# MCU.net
KiCad netlist of a schematic drawn in Altium Designer
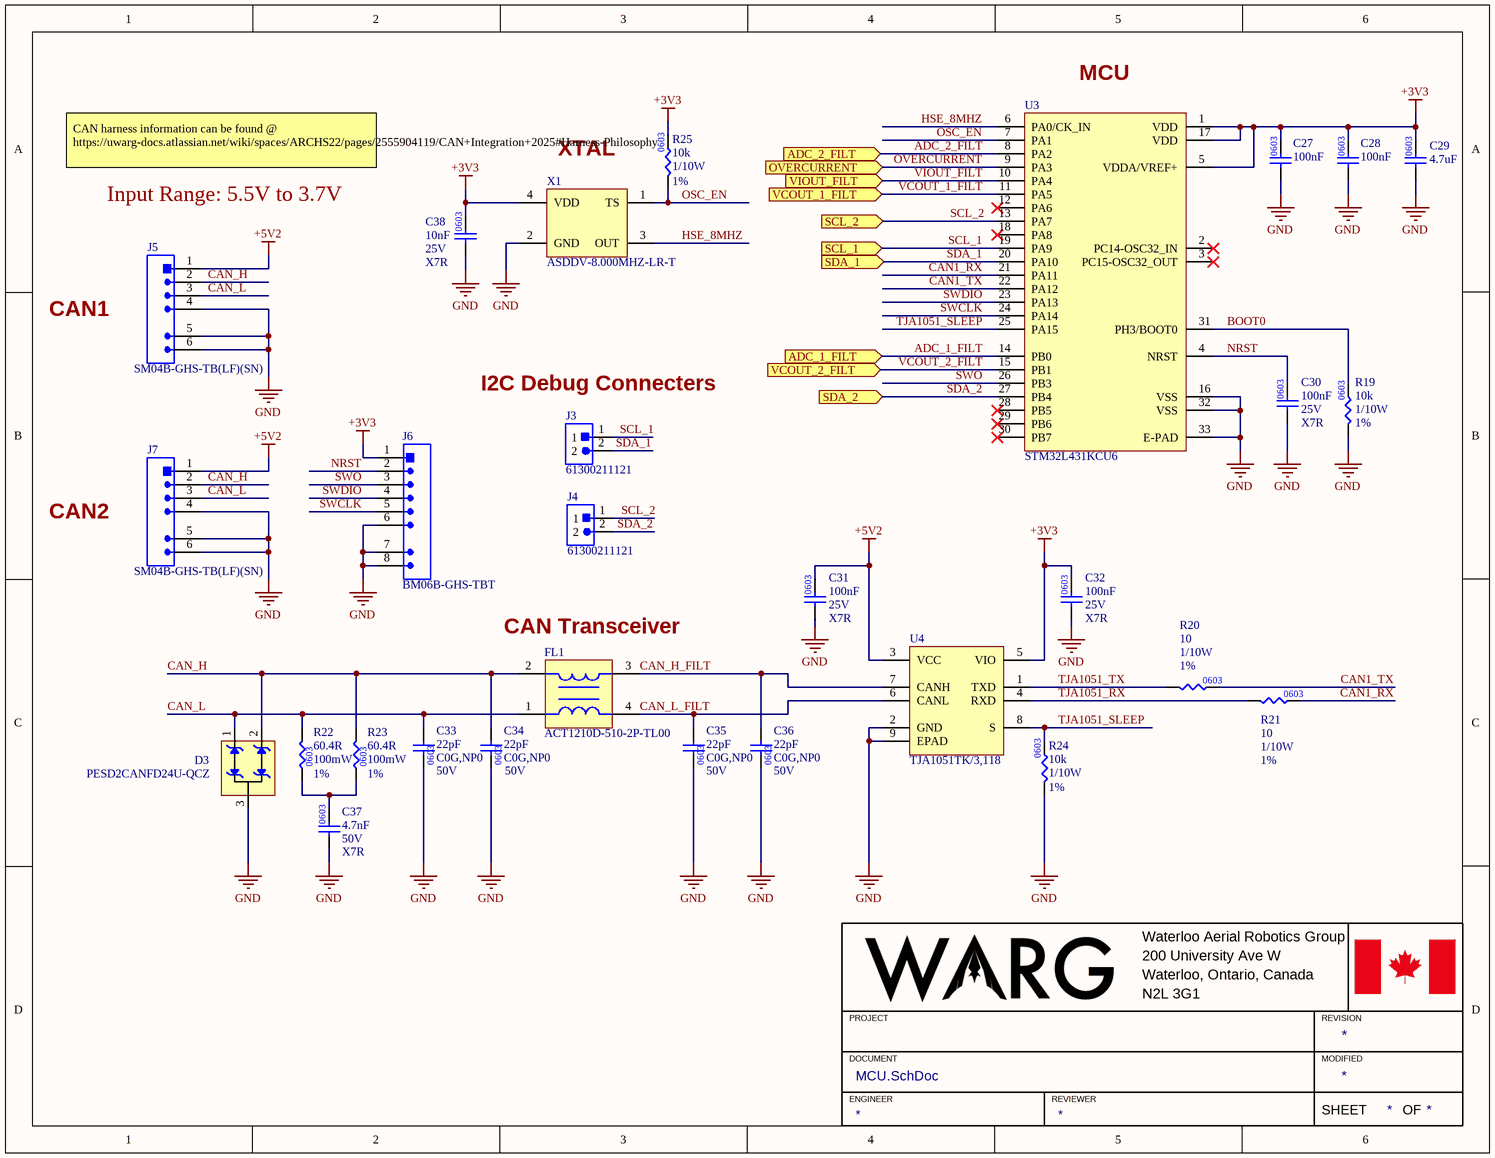
[diagram p0: MCU.SchDoc]

(export (version "E")
  (design (tool "Eeschema 10.0.6"))
  (components
    (comp (ref "C27")
      (value "100nF")
      (footprint ".CAP_0603-Footprint-1")
      (description "CAP CER 100nF 16V X7R 0603")
      (fields (field (name "VOLTAGE") "16V") (field (name "Comment") "GCM188R71C104KA37D"))
      (libsource (lib "WARG") (part ".CAP_0603-Symbol-1"))
    )
    (comp (ref "C28")
      (value "100nF")
      (footprint ".CAP_0603-Footprint-1")
      (description "CAP CER 100nF 16V X7R 0603")
      (fields (field (name "VOLTAGE") "16V") (field (name "Comment") "GCM188R71C104KA37D"))
      (libsource (lib "WARG") (part ".CAP_0603-Symbol-1"))
    )
    (comp (ref "C29")
      (value "4.7uF")
      (footprint ".CAP_0603-Footprint-1")
      (description "CAP CER 4.7uF 25V X6S 0603")
      (fields (field (name "VOLTAGE") "25V") (field (name "Comment") "GRM188C81E475KE11D"))
      (libsource (lib "WARG") (part ".CAP_0603-Symbol-1"))
    )
    (comp (ref "C30")
      (value "CL10B104KA8NNNC")
      (footprint ".CAP_0603-Footprint-1")
      (description "CAP CER 0.1UF 25V X7R 0603")
      (fields
        (field (name "TOLERANCE") "10%")
        (field (name "VOLTAGE RATING") "25V")
        (field (name "DIELECTRIC") "X7R")
        (field (name "CAPACITANCE") "100nF")
      )
      (libsource (lib "WARG") (part ".CAP_0603-Symbol-1"))
    )
    (comp (ref "C31")
      (value "CL10B104KA8NNNC")
      (footprint ".CAP_0603-Footprint-1")
      (description "CAP CER 0.1UF 25V X7R 0603")
      (fields
        (field (name "TOLERANCE") "10%")
        (field (name "VOLTAGE RATING") "25V")
        (field (name "DIELECTRIC") "X7R")
        (field (name "CAPACITANCE") "100nF")
      )
      (libsource (lib "WARG") (part ".CAP_0603-Symbol-1"))
    )
    (comp (ref "C32")
      (value "CL10B104KA8NNNC")
      (footprint ".CAP_0603-Footprint-1")
      (description "CAP CER 0.1UF 25V X7R 0603")
      (fields
        (field (name "TOLERANCE") "10%")
        (field (name "VOLTAGE RATING") "25V")
        (field (name "DIELECTRIC") "X7R")
        (field (name "CAPACITANCE") "100nF")
      )
      (libsource (lib "WARG") (part ".CAP_0603-Symbol-1"))
    )
    (comp (ref "C33")
      (value "22pF")
      (footprint ".CAP_0603-Footprint-1")
      (description "CAP CER 22PF 50V C0G/NPO 0603")
      (fields
        (field (name "TEMPERATURE COEFFICIENT") "C0G,NP0")
        (field (name "TOLERANCE") "5%")
        (field (name "VOLTAGE RATING") "50V")
        (field (name "Comment") "CC0603JRNPO9BN220")
      )
      (libsource (lib "WARG") (part ".CAP_0603-Symbol-1"))
    )
    (comp (ref "C34")
      (value "22pF")
      (footprint ".CAP_0603-Footprint-1")
      (description "CAP CER 22PF 50V C0G/NPO 0603")
      (fields
        (field (name "TEMPERATURE COEFFICIENT") "C0G,NP0")
        (field (name "TOLERANCE") "5%")
        (field (name "VOLTAGE RATING") "50V")
        (field (name "Comment") "CC0603JRNPO9BN220")
      )
      (libsource (lib "WARG") (part ".CAP_0603-Symbol-1"))
    )
    (comp (ref "C35")
      (value "22pF")
      (footprint ".CAP_0603-Footprint-1")
      (description "CAP CER 22PF 50V C0G/NPO 0603")
      (fields
        (field (name "TEMPERATURE COEFFICIENT") "C0G,NP0")
        (field (name "TOLERANCE") "5%")
        (field (name "VOLTAGE RATING") "50V")
        (field (name "Comment") "CC0603JRNPO9BN220")
      )
      (libsource (lib "WARG") (part ".CAP_0603-Symbol-1"))
    )
    (comp (ref "C36")
      (value "22pF")
      (footprint ".CAP_0603-Footprint-1")
      (description "CAP CER 22PF 50V C0G/NPO 0603")
      (fields
        (field (name "TEMPERATURE COEFFICIENT") "C0G,NP0")
        (field (name "TOLERANCE") "5%")
        (field (name "VOLTAGE RATING") "50V")
        (field (name "Comment") "CC0603JRNPO9BN220")
      )
      (libsource (lib "WARG") (part ".CAP_0603-Symbol-1"))
    )
    (comp (ref "C37")
      (value "4.7nF")
      (footprint ".CAP_0603-Footprint-1")
      (description "CAP CER 4700PF 50V X7R 0603")
      (fields
        (field (name "RATED DC VOLTAGE (URDC)") "50V")
        (field (name "TEMPERATURE CHARACTERISTICS CODE") "X7R")
        (field (name "Comment") "GCM188R71H472KA37D")
      )
      (libsource (lib "WARG") (part ".CAP_0603-Symbol-1"))
    )
    (comp (ref "C38")
      (value "CC0603KRX7R8BB103")
      (footprint ".CAP_0603-Footprint-1")
      (description "CAP CER 10nF 25V X7R 0603")
      (fields
        (field (name "TEMPERATURE COEFFICIENT") "X7R")
        (field (name "VOLTAGE RATING") "25V")
        (field (name "CAPACITANCE") "10nF")
      )
      (libsource (lib "WARG") (part ".CAP_0603-Symbol-1"))
    )
    (comp (ref "D3")
      (value "PESD2CANFD24U-QCZ")
      (footprint "PESD2CANFD24U-QCZ-Footprint-1")
      (description "TVS DIODE 24VWM 43VC DFN1412D-3")
      (libsource (lib "WARG") (part "PESD2CANFD24U-QCZ-Symbol-1"))
    )
    (comp (ref "FL1")
      (value "ACT1210D-510-2P-TL00")
      (footprint "ACT1210D-510-2P-TL00-Footprint-1")
      (description "CMC 50UH 115MA 2LN 2.3KOHM SMD")
      (libsource (lib "WARG") (part "ACT1210D-510-2P-TL00-Symbol-1"))
    )
    (comp (ref "J3")
      (value "61300211121")
      (footprint "61300211121")
      (description "CONN HEADER VERT 2POS 2.54MM")
      (libsource (lib "WARG") (part "61300211121"))
    )
    (comp (ref "J4")
      (value "61300211121")
      (footprint "61300211121")
      (description "CONN HEADER VERT 2POS 2.54MM")
      (libsource (lib "WARG") (part "61300211121"))
    )
    (comp (ref "J5")
      (value "SM04B-GHS-TB(LF)(SN)")
      (footprint "CONN_SM04B-GHS-TB_JST")
      (description "Conn Shrouded Header HDR 4 POS 1.25mm Solder RA SMD Reel")
      (libsource (lib "WARG") (part "SM04B-GHS-TB(LF)(SN)"))
    )
    (comp (ref "J6")
      (value "BM06B-GHS-TBT")
      (footprint "BM06B-GHS-TBT-Footprint-1")
      (description "Connector Header Surface Mount 6 position 0.049\" (1.25mm)")
      (libsource (lib "WARG") (part "BM06B-GHS-TBT-Symbol-1"))
    )
    (comp (ref "J7")
      (value "SM04B-GHS-TB(LF)(SN)")
      (footprint "CONN_SM04B-GHS-TB_JST")
      (description "Conn Shrouded Header HDR 4 POS 1.25mm Solder RA SMD Reel")
      (libsource (lib "WARG") (part "SM04B-GHS-TB(LF)(SN)"))
    )
    (comp (ref "R19")
      (value "10k")
      (footprint ".RES_0603-Footprint-1")
      (description "RES 10K OHM 1% 1/10W 0603")
      (fields
        (field (name "POWER") "1/10W")
        (field (name "TOLERANCE") "1%")
        (field (name "Comment") "RC0603FR-0710KL")
      )
      (libsource (lib "WARG") (part ".RES_0603-Symbol-1"))
    )
    (comp (ref "R20")
      (value "10")
      (footprint ".RES_0603-Footprint-1")
      (description "RES 10 OHM 1% 1/10W 0603")
      (fields
        (field (name "POWER") "1/10W")
        (field (name "TOLERANCE") "1%")
        (field (name "Comment") "RC0603FR-0710RL")
      )
      (libsource (lib "WARG") (part ".RES_0603-Symbol-1"))
    )
    (comp (ref "R21")
      (value "10")
      (footprint ".RES_0603-Footprint-1")
      (description "RES 10 OHM 1% 1/10W 0603")
      (fields
        (field (name "POWER") "1/10W")
        (field (name "TOLERANCE") "1%")
        (field (name "Comment") "RC0603FR-0710RL")
      )
      (libsource (lib "WARG") (part ".RES_0603-Symbol-1"))
    )
    (comp (ref "R22")
      (value "60.4R")
      (footprint "RES0603")
      (description "RES 60.4 OHM 1% 1/10W 0603")
      (fields
        (field (name "TOLERANCE") "1%")
        (field (name "POWER") "100mW")
        (field (name "Comment") "RC0603FR-1360R4L")
      )
      (libsource (lib "WARG") (part "RES-2"))
    )
    (comp (ref "R23")
      (value "60.4R")
      (footprint "RES0603")
      (description "RES 60.4 OHM 1% 1/10W 0603")
      (fields
        (field (name "TOLERANCE") "1%")
        (field (name "POWER") "100mW")
        (field (name "Comment") "RC0603FR-1360R4L")
      )
      (libsource (lib "WARG") (part "RES-2"))
    )
    (comp (ref "R24")
      (value "10k")
      (footprint ".RES_0603-Footprint-1")
      (description "RES 10K OHM 1% 1/10W 0603")
      (fields
        (field (name "POWER") "1/10W")
        (field (name "TOLERANCE") "1%")
        (field (name "Comment") "RC0603FR-0710KL")
      )
      (libsource (lib "WARG") (part ".RES_0603-Symbol-1"))
    )
    (comp (ref "R25")
      (value "10k")
      (footprint ".RES_0603-Footprint-1")
      (description "RES 10K OHM 1% 1/10W 0603")
      (fields
        (field (name "POWER") "1/10W")
        (field (name "TOLERANCE") "1%")
        (field (name "Comment") "RC0603FR-0710KL")
      )
      (libsource (lib "WARG") (part ".RES_0603-Symbol-1"))
    )
    (comp (ref "U3")
      (value "STM32L431KCU6")
      (footprint "STM32L431KCU6-Footprint-1")
      (description "IC MCU 32BIT 256KB FLSH 32UFQFPN")
      (libsource (lib "WARG") (part "STM32L431KCU6-Symbol-1"))
    )
    (comp (ref "U4")
      (value "TJA1051TK/3,118")
      (footprint "TJA1051TK_3,118-Footprint-1")
      (description "IC TRANSCEIVER HALF 1/1 8HVSON")
      (libsource (lib "WARG") (part "TJA1051TK_3,118-Symbol-1"))
    )
    (comp (ref "X1")
      (value "ASDDV-8.000MHZ-LR-T")
      (footprint "ASDDV-8.000MHZ-LR-T-Footprint-1")
      (description "OSC XO 8.000MHZ CMOS SMD")
      (libsource (lib "WARG") (part "ASDDV-8.000MHZ-LR-T-Symbol-1"))
    )
  )
  (nets
    (net (code "1") (name "+3V3") (class "Default")
      (node (ref "C27") (pin "2") (pinfunction "2_2") (pintype "passive"))
      (node (ref "C28") (pin "2") (pinfunction "2_2") (pintype "passive"))
      (node (ref "C29") (pin "2") (pinfunction "2_2") (pintype "passive"))
      (node (ref "C32") (pin "2") (pinfunction "2_2") (pintype "passive"))
      (node (ref "C38") (pin "2") (pinfunction "2_2") (pintype "passive"))
      (node (ref "J6") (pin "1") (pinfunction "1_1") (pintype "passive"))
      (node (ref "R25") (pin "2") (pinfunction "2_2") (pintype "passive"))
      (node (ref "U3") (pin "1") (pinfunction "VDD_1") (pintype "passive"))
      (node (ref "U3") (pin "17") (pinfunction "VDD_17") (pintype "passive"))
      (node (ref "U3") (pin "5") (pinfunction "VDDA/VREF+_5") (pintype "passive"))
      (node (ref "U4") (pin "5") (pinfunction "VIO_5") (pintype "passive"))
      (node (ref "X1") (pin "4") (pinfunction "VDD_4") (pintype "passive"))
    )
    (net (code "2") (name "+5V2") (class "Default")
      (node (ref "C31") (pin "2") (pinfunction "2_2") (pintype "passive"))
      (node (ref "J5") (pin "1") (pinfunction "1_1") (pintype "passive"))
      (node (ref "J7") (pin "1") (pinfunction "1_1") (pintype "passive"))
      (node (ref "U4") (pin "3") (pinfunction "VCC_3") (pintype "passive"))
    )
    (net (code "3") (name "/ADC_1_FILT") (class "Default")
      (node (ref "U3") (pin "14") (pinfunction "PB0_14") (pintype "passive"))
    )
    (net (code "4") (name "/ADC_2_FILT") (class "Default")
      (node (ref "U3") (pin "8") (pinfunction "PA2_8") (pintype "passive"))
    )
    (net (code "5") (name "/BOOT0") (class "Default")
      (node (ref "R19") (pin "2") (pinfunction "2_2") (pintype "passive"))
      (node (ref "U3") (pin "31") (pinfunction "PH3/BOOT0_31") (pintype "passive"))
    )
    (net (code "6") (name "/CAN1_RX") (class "Default")
      (node (ref "R21") (pin "2") (pinfunction "2_2") (pintype "passive"))
      (node (ref "U3") (pin "21") (pinfunction "PA11_21") (pintype "passive"))
    )
    (net (code "7") (name "/CAN1_TX") (class "Default")
      (node (ref "R20") (pin "2") (pinfunction "2_2") (pintype "passive"))
      (node (ref "U3") (pin "22") (pinfunction "PA12_22") (pintype "passive"))
    )
    (net (code "8") (name "/CAN_H") (class "Default")
      (node (ref "C34") (pin "2") (pinfunction "2_2") (pintype "passive"))
      (node (ref "D3") (pin "2") (pinfunction "K2_2") (pintype "passive"))
      (node (ref "FL1") (pin "2") (pinfunction "2_2") (pintype "passive"))
      (node (ref "J5") (pin "2") (pinfunction "2_2") (pintype "passive"))
      (node (ref "J7") (pin "2") (pinfunction "2_2") (pintype "passive"))
      (node (ref "R23") (pin "2") (pinfunction "2_2") (pintype "passive"))
    )
    (net (code "9") (name "/CAN_H_FILT") (class "Default")
      (node (ref "C36") (pin "2") (pinfunction "2_2") (pintype "passive"))
      (node (ref "FL1") (pin "3") (pinfunction "3_3") (pintype "passive"))
      (node (ref "U4") (pin "7") (pinfunction "CANH_7") (pintype "passive"))
    )
    (net (code "10") (name "/CAN_L") (class "Default")
      (node (ref "C33") (pin "2") (pinfunction "2_2") (pintype "passive"))
      (node (ref "D3") (pin "1") (pinfunction "K1_1") (pintype "passive"))
      (node (ref "FL1") (pin "1") (pinfunction "1_1") (pintype "passive"))
      (node (ref "J5") (pin "3") (pinfunction "3_3") (pintype "passive"))
      (node (ref "J7") (pin "3") (pinfunction "3_3") (pintype "passive"))
      (node (ref "R22") (pin "2") (pinfunction "2_2") (pintype "passive"))
    )
    (net (code "11") (name "/CAN_L_FILT") (class "Default")
      (node (ref "C35") (pin "2") (pinfunction "2_2") (pintype "passive"))
      (node (ref "FL1") (pin "4") (pinfunction "4_4") (pintype "passive"))
      (node (ref "U4") (pin "6") (pinfunction "CANL_6") (pintype "passive"))
    )
    (net (code "12") (name "/HSE_8MHZ") (class "Default")
      (node (ref "U3") (pin "6") (pinfunction "PA0/CK_IN_6") (pintype "passive"))
      (node (ref "X1") (pin "3") (pinfunction "OUT_3") (pintype "passive"))
    )
    (net (code "13") (name "/NRST") (class "Default")
      (node (ref "C30") (pin "2") (pinfunction "2_2") (pintype "passive"))
      (node (ref "J6") (pin "2") (pinfunction "2_2") (pintype "passive"))
      (node (ref "U3") (pin "4") (pinfunction "NRST_4") (pintype "passive"))
    )
    (net (code "14") (name "/OSC_EN") (class "Default")
      (node (ref "R25") (pin "1") (pinfunction "1_1") (pintype "passive"))
      (node (ref "U3") (pin "7") (pinfunction "PA1_7") (pintype "passive"))
      (node (ref "X1") (pin "1") (pinfunction "TS_1") (pintype "passive"))
    )
    (net (code "15") (name "/OVERCURRENT") (class "Default")
      (node (ref "U3") (pin "9") (pinfunction "PA3_9") (pintype "passive"))
    )
    (net (code "16") (name "/SCL_1") (class "Default")
      (node (ref "J3") (pin "1") (pinfunction "1_1") (pintype "passive"))
      (node (ref "U3") (pin "19") (pinfunction "PA9_19") (pintype "passive"))
    )
    (net (code "17") (name "/SCL_2") (class "Default")
      (node (ref "J4") (pin "1") (pinfunction "1_1") (pintype "passive"))
      (node (ref "U3") (pin "13") (pinfunction "PA7_13") (pintype "passive"))
    )
    (net (code "18") (name "/SDA_1") (class "Default")
      (node (ref "J3") (pin "2") (pinfunction "2_2") (pintype "passive"))
      (node (ref "U3") (pin "20") (pinfunction "PA10_20") (pintype "passive"))
    )
    (net (code "19") (name "/SDA_2") (class "Default")
      (node (ref "J4") (pin "2") (pinfunction "2_2") (pintype "passive"))
      (node (ref "U3") (pin "27") (pinfunction "PB4_27") (pintype "passive"))
    )
    (net (code "20") (name "/SWCLK") (class "Default")
      (node (ref "J6") (pin "5") (pinfunction "5_5") (pintype "passive"))
      (node (ref "U3") (pin "24") (pinfunction "PA14_24") (pintype "passive"))
    )
    (net (code "21") (name "/SWDIO") (class "Default")
      (node (ref "J6") (pin "4") (pinfunction "4_4") (pintype "passive"))
      (node (ref "U3") (pin "23") (pinfunction "PA13_23") (pintype "passive"))
    )
    (net (code "22") (name "/SWO") (class "Default")
      (node (ref "J6") (pin "3") (pinfunction "3_3") (pintype "passive"))
      (node (ref "U3") (pin "26") (pinfunction "PB3_26") (pintype "passive"))
    )
    (net (code "23") (name "/TJA1051_RX") (class "Default")
      (node (ref "R21") (pin "1") (pinfunction "1_1") (pintype "passive"))
      (node (ref "U4") (pin "4") (pinfunction "RXD_4") (pintype "passive"))
    )
    (net (code "24") (name "/TJA1051_SLEEP") (class "Default")
      (node (ref "R24") (pin "2") (pinfunction "2_2") (pintype "passive"))
      (node (ref "U3") (pin "25") (pinfunction "PA15_25") (pintype "passive"))
      (node (ref "U4") (pin "8") (pinfunction "S_8") (pintype "passive"))
    )
    (net (code "25") (name "/TJA1051_TX") (class "Default")
      (node (ref "R20") (pin "1") (pinfunction "1_1") (pintype "passive"))
      (node (ref "U4") (pin "1") (pinfunction "TXD_1") (pintype "passive"))
    )
    (net (code "26") (name "/VCOUT_1_FILT") (class "Default")
      (node (ref "U3") (pin "11") (pinfunction "PA5_11") (pintype "passive"))
    )
    (net (code "27") (name "/VCOUT_2_FILT") (class "Default")
      (node (ref "U3") (pin "15") (pinfunction "PB1_15") (pintype "passive"))
    )
    (net (code "28") (name "/VIOUT_FILT") (class "Default")
      (node (ref "U3") (pin "10") (pinfunction "PA4_10") (pintype "passive"))
    )
    (net (code "29") (name "GND") (class "Default")
      (node (ref "C27") (pin "1") (pinfunction "1_1") (pintype "passive"))
      (node (ref "C28") (pin "1") (pinfunction "1_1") (pintype "passive"))
      (node (ref "C29") (pin "1") (pinfunction "1_1") (pintype "passive"))
      (node (ref "C30") (pin "1") (pinfunction "1_1") (pintype "passive"))
      (node (ref "C31") (pin "1") (pinfunction "1_1") (pintype "passive"))
      (node (ref "C32") (pin "1") (pinfunction "1_1") (pintype "passive"))
      (node (ref "C33") (pin "1") (pinfunction "1_1") (pintype "passive"))
      (node (ref "C34") (pin "1") (pinfunction "1_1") (pintype "passive"))
      (node (ref "C35") (pin "1") (pinfunction "1_1") (pintype "passive"))
      (node (ref "C36") (pin "1") (pinfunction "1_1") (pintype "passive"))
      (node (ref "C37") (pin "1") (pinfunction "1_1") (pintype "passive"))
      (node (ref "C38") (pin "1") (pinfunction "1_1") (pintype "passive"))
      (node (ref "D3") (pin "3") (pinfunction "CC_3") (pintype "passive"))
      (node (ref "J5") (pin "4") (pinfunction "4_4") (pintype "passive"))
      (node (ref "J5") (pin "5") (pinfunction "5_5") (pintype "passive"))
      (node (ref "J5") (pin "6") (pinfunction "6_6") (pintype "passive"))
      (node (ref "J6") (pin "6") (pinfunction "6_6") (pintype "passive"))
      (node (ref "J6") (pin "7") (pinfunction "7_7") (pintype "passive"))
      (node (ref "J6") (pin "8") (pinfunction "8_8") (pintype "passive"))
      (node (ref "J7") (pin "4") (pinfunction "4_4") (pintype "passive"))
      (node (ref "J7") (pin "5") (pinfunction "5_5") (pintype "passive"))
      (node (ref "J7") (pin "6") (pinfunction "6_6") (pintype "passive"))
      (node (ref "R19") (pin "1") (pinfunction "1_1") (pintype "passive"))
      (node (ref "R24") (pin "1") (pinfunction "1_1") (pintype "passive"))
      (node (ref "U3") (pin "16") (pinfunction "VSS_16") (pintype "passive"))
      (node (ref "U3") (pin "32") (pinfunction "VSS_32") (pintype "passive"))
      (node (ref "U3") (pin "33") (pinfunction "E-PAD_33") (pintype "passive"))
      (node (ref "U4") (pin "2") (pinfunction "GND_2") (pintype "passive"))
      (node (ref "U4") (pin "9") (pinfunction "EPAD_9") (pintype "passive"))
      (node (ref "X1") (pin "2") (pinfunction "GND_2") (pintype "passive"))
    )
    (net (code "30") (name "Net-(C37-Pad2)") (class "Default")
      (node (ref "C37") (pin "2") (pinfunction "2_2") (pintype "passive"))
      (node (ref "R22") (pin "1") (pinfunction "1_1") (pintype "passive"))
      (node (ref "R23") (pin "1") (pinfunction "1_1") (pintype "passive"))
    )
    (net (code "31") (name "unconnected-(U3-PA6-Pad12)") (class "Default")
      (node (ref "U3") (pin "12") (pinfunction "PA6_12") (pintype "passive+no_connect"))
    )
    (net (code "32") (name "unconnected-(U3-PA8-Pad18)") (class "Default")
      (node (ref "U3") (pin "18") (pinfunction "PA8_18") (pintype "passive+no_connect"))
    )
    (net (code "33") (name "unconnected-(U3-PB5-Pad28)") (class "Default")
      (node (ref "U3") (pin "28") (pinfunction "PB5_28") (pintype "passive+no_connect"))
    )
    (net (code "34") (name "unconnected-(U3-PB6-Pad29)") (class "Default")
      (node (ref "U3") (pin "29") (pinfunction "PB6_29") (pintype "passive+no_connect"))
    )
    (net (code "35") (name "unconnected-(U3-PB7-Pad30)") (class "Default")
      (node (ref "U3") (pin "30") (pinfunction "PB7_30") (pintype "passive+no_connect"))
    )
    (net (code "36") (name "unconnected-(U3-PC14-OSC32_IN-Pad2)") (class "Default")
      (node (ref "U3") (pin "2") (pinfunction "PC14-OSC32_IN_2") (pintype "passive+no_connect"))
    )
    (net (code "37") (name "unconnected-(U3-PC15-OSC32_OUT-Pad3)") (class "Default")
      (node (ref "U3") (pin "3") (pinfunction "PC15-OSC32_OUT_3") (pintype "passive+no_connect"))
    )
  )
)
